# PiHAT_Sensor.net
KiCad netlist of a schematic drawn in Altium Designer
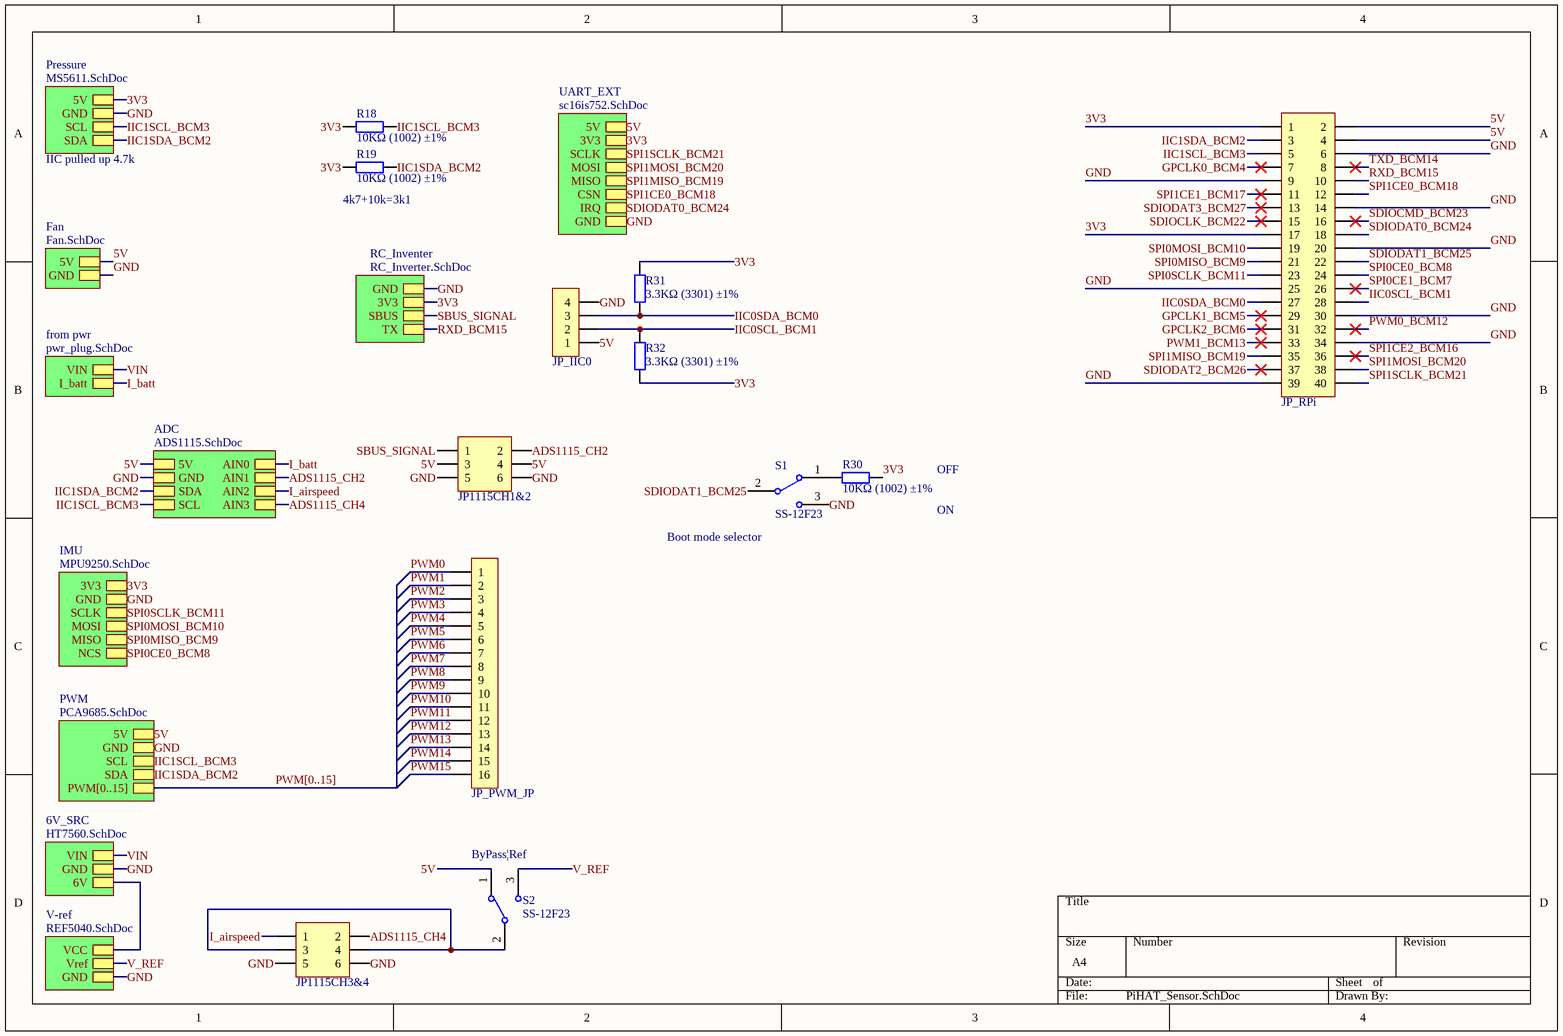
[diagram p0: PiHAT_Sensor.SchDoc]

(export (version "E")
  (design (tool "Eeschema 10.0.6"))
  (components
    (comp (ref "JP1115CH1&2")
      (value "Header3X2")
      (footprint "HDR2.54-WI-2x3P")
      (description "3*2P接插件")
      (fields (field (name "版权归属") "源创客"))
      (libsource (lib "4.5   - 接插件-脚距2.54") (part "Header 3X2"))
    )
    (comp (ref "JP1115CH3&4")
      (value "Header3X2")
      (footprint "HDR2.54-WI-2x3P")
      (description "3*2P接插件")
      (fields (field (name "版权归属") "源创客"))
      (libsource (lib "4.5   - 接插件-脚距2.54") (part "Header 3X2"))
    )
    (comp (ref "JP_IIC0")
      (value "HDR-1X4")
      (footprint "MX 1.25-WS-4P")
      (description "4P接插件")
      (fields (field (name "版权归属") "源创客"))
      (libsource (lib "4.2   - 接插件-脚距1.25") (part "Header 4"))
    )
    (comp (ref "JP_PWM_JP")
      (value "HDR-1X16")
      (footprint "HDR2.54-LI-16P")
      (description "16P接插件")
      (fields (field (name "版权归属") "源创客"))
      (libsource (lib "4.5   - 接插件-脚距2.54") (part "Header 16"))
    )
    (comp (ref "JP_RPi")
      (value "Header 2X11")
      (footprint "HDR2.54-LI-2x20P")
      (description "20*2P接插件")
      (fields (field (name "版权归属") "源创客"))
      (libsource (lib "4.5   - 接插件-脚距2.54") (part "Header 20X2"))
    )
    (comp (ref "R18")
      (value "10KΩ (1002) ±1%")
      (footprint "0402_R")
      (description "贴片电阻")
      (libsource (lib "Miscellaneous Devices LC") (part "0402 10KΩ (1002) 1%"))
    )
    (comp (ref "R19")
      (value "10KΩ (1002) ±1%")
      (footprint "0402_R")
      (description "贴片电阻")
      (libsource (lib "Miscellaneous Devices LC") (part "0402 10KΩ (1002) 1%"))
    )
    (comp (ref "R30")
      (value "10KΩ (1002) ±1%")
      (footprint "0402_R")
      (description "贴片电阻")
      (libsource (lib "Miscellaneous Devices LC") (part "0402 10KΩ (1002) 1%"))
    )
    (comp (ref "R31")
      (value "3.3KΩ (3301) ±1%")
      (footprint "0402_R")
      (description "贴片电阻")
      (libsource (lib "Miscellaneous Devices LC") (part "0402 3.3KΩ (3301) 1%"))
    )
    (comp (ref "R32")
      (value "3.3KΩ (3301) ±1%")
      (footprint "0402_R")
      (description "贴片电阻")
      (libsource (lib "Miscellaneous Devices LC") (part "0402 3.3KΩ (3301) 1%"))
    )
    (comp (ref "S1")
      (value "SS-12F23")
      (footprint "MSK-12C01-07")
      (description "1路波动开关")
      (fields (field (name "版权归属") "源创客"))
      (libsource (lib "5.1   - 按键-开关") (part "SSW-1P"))
    )
    (comp (ref "S2")
      (value "SS-12F23")
      (footprint "MSK-12C01-07")
      (description "1路波动开关")
      (fields (field (name "版权归属") "源创客"))
      (libsource (lib "5.1   - 按键-开关") (part "SSW-1P"))
    )
  )
  (nets
    (net (code "1") (name "/3V3") (class "Default")
      (node (ref "JP_RPi") (pin "1") (pinfunction "1_1") (pintype "passive"))
      (node (ref "JP_RPi") (pin "17") (pinfunction "17_17") (pintype "passive"))
      (node (ref "R18") (pin "1") (pinfunction "1_1") (pintype "passive"))
      (node (ref "R19") (pin "1") (pinfunction "1_1") (pintype "passive"))
      (node (ref "R30") (pin "2") (pinfunction "2_2") (pintype "passive"))
      (node (ref "R31") (pin "2") (pinfunction "2_2") (pintype "passive"))
      (node (ref "R32") (pin "1") (pinfunction "1_1") (pintype "passive"))
    )
    (net (code "2") (name "/5V") (class "Default")
      (node (ref "JP1115CH1&2") (pin "3") (pinfunction "3_3") (pintype "passive"))
      (node (ref "JP1115CH1&2") (pin "4") (pinfunction "4_4") (pintype "passive"))
      (node (ref "JP_IIC0") (pin "1") (pinfunction "1_1") (pintype "passive"))
      (node (ref "JP_RPi") (pin "2") (pinfunction "2_2") (pintype "passive"))
      (node (ref "JP_RPi") (pin "4") (pinfunction "4_4") (pintype "passive"))
      (node (ref "S2") (pin "1") (pinfunction "1_1") (pintype "passive"))
    )
    (net (code "4") (name "/ADS1115_CH2") (class "Default")
      (node (ref "JP1115CH1&2") (pin "2") (pinfunction "2_2") (pintype "passive"))
    )
    (net (code "5") (name "/ADS1115_CH4") (class "Default")
      (node (ref "JP1115CH3&4") (pin "2") (pinfunction "2_2") (pintype "passive"))
    )
    (net (code "6") (name "/GND") (class "Default")
      (node (ref "JP1115CH1&2") (pin "5") (pinfunction "5_5") (pintype "passive"))
      (node (ref "JP1115CH1&2") (pin "6") (pinfunction "6_6") (pintype "passive"))
      (node (ref "JP1115CH3&4") (pin "5") (pinfunction "5_5") (pintype "passive"))
      (node (ref "JP1115CH3&4") (pin "6") (pinfunction "6_6") (pintype "passive"))
      (node (ref "JP_IIC0") (pin "4") (pinfunction "4_4") (pintype "passive"))
      (node (ref "JP_RPi") (pin "14") (pinfunction "14_14") (pintype "passive"))
      (node (ref "JP_RPi") (pin "20") (pinfunction "20_20") (pintype "passive"))
      (node (ref "JP_RPi") (pin "25") (pinfunction "25_25") (pintype "passive"))
      (node (ref "JP_RPi") (pin "30") (pinfunction "30_30") (pintype "passive"))
      (node (ref "JP_RPi") (pin "34") (pinfunction "34_34") (pintype "passive"))
      (node (ref "JP_RPi") (pin "39") (pinfunction "39_39") (pintype "passive"))
      (node (ref "JP_RPi") (pin "6") (pinfunction "6_6") (pintype "passive"))
      (node (ref "JP_RPi") (pin "9") (pinfunction "9_9") (pintype "passive"))
      (node (ref "S1") (pin "3") (pinfunction "3_3") (pintype "passive"))
    )
    (net (code "7") (name "/GPCLK0_BCM4") (class "Default")
      (node (ref "JP_RPi") (pin "7") (pinfunction "7_7") (pintype "passive+no_connect"))
    )
    (net (code "8") (name "/GPCLK1_BCM5") (class "Default")
      (node (ref "JP_RPi") (pin "29") (pinfunction "29_29") (pintype "passive+no_connect"))
    )
    (net (code "9") (name "/GPCLK2_BCM6") (class "Default")
      (node (ref "JP_RPi") (pin "31") (pinfunction "31_31") (pintype "passive+no_connect"))
    )
    (net (code "10") (name "/IIC0SCL_BCM1") (class "Default")
      (node (ref "JP_IIC0") (pin "2") (pinfunction "2_2") (pintype "passive"))
      (node (ref "JP_RPi") (pin "28") (pinfunction "28_28") (pintype "passive"))
      (node (ref "R32") (pin "2") (pinfunction "2_2") (pintype "passive"))
    )
    (net (code "11") (name "/IIC0SDA_BCM0") (class "Default")
      (node (ref "JP_IIC0") (pin "3") (pinfunction "3_3") (pintype "passive"))
      (node (ref "JP_RPi") (pin "27") (pinfunction "27_27") (pintype "passive"))
      (node (ref "R31") (pin "1") (pinfunction "1_1") (pintype "passive"))
    )
    (net (code "12") (name "/IIC1SCL_BCM3") (class "Default")
      (node (ref "JP_RPi") (pin "5") (pinfunction "5_5") (pintype "passive"))
      (node (ref "R18") (pin "2") (pinfunction "2_2") (pintype "passive"))
    )
    (net (code "13") (name "/IIC1SDA_BCM2") (class "Default")
      (node (ref "JP_RPi") (pin "3") (pinfunction "3_3") (pintype "passive"))
      (node (ref "R19") (pin "2") (pinfunction "2_2") (pintype "passive"))
    )
    (net (code "14") (name "/I_airspeed") (class "Default")
      (node (ref "JP1115CH3&4") (pin "1") (pinfunction "1_1") (pintype "passive"))
    )
    (net (code "16") (name "/PWM0") (class "Default")
      (node (ref "JP_PWM_JP") (pin "1") (pinfunction "1_1") (pintype "passive"))
    )
    (net (code "17") (name "/PWM0_BCM12") (class "Default")
      (node (ref "JP_RPi") (pin "32") (pinfunction "32_32") (pintype "passive+no_connect"))
    )
    (net (code "18") (name "/PWM1") (class "Default")
      (node (ref "JP_PWM_JP") (pin "2") (pinfunction "2_2") (pintype "passive"))
    )
    (net (code "19") (name "/PWM1_BCM13") (class "Default")
      (node (ref "JP_RPi") (pin "33") (pinfunction "33_33") (pintype "passive+no_connect"))
    )
    (net (code "20") (name "/PWM2") (class "Default")
      (node (ref "JP_PWM_JP") (pin "3") (pinfunction "3_3") (pintype "passive"))
    )
    (net (code "21") (name "/PWM3") (class "Default")
      (node (ref "JP_PWM_JP") (pin "4") (pinfunction "4_4") (pintype "passive"))
    )
    (net (code "22") (name "/PWM4") (class "Default")
      (node (ref "JP_PWM_JP") (pin "5") (pinfunction "5_5") (pintype "passive"))
    )
    (net (code "23") (name "/PWM5") (class "Default")
      (node (ref "JP_PWM_JP") (pin "6") (pinfunction "6_6") (pintype "passive"))
    )
    (net (code "24") (name "/PWM6") (class "Default")
      (node (ref "JP_PWM_JP") (pin "7") (pinfunction "7_7") (pintype "passive"))
    )
    (net (code "25") (name "/PWM7") (class "Default")
      (node (ref "JP_PWM_JP") (pin "8") (pinfunction "8_8") (pintype "passive"))
    )
    (net (code "26") (name "/PWM8") (class "Default")
      (node (ref "JP_PWM_JP") (pin "9") (pinfunction "9_9") (pintype "passive"))
    )
    (net (code "27") (name "/PWM9") (class "Default")
      (node (ref "JP_PWM_JP") (pin "10") (pinfunction "10_10") (pintype "passive"))
    )
    (net (code "28") (name "/PWM10") (class "Default")
      (node (ref "JP_PWM_JP") (pin "11") (pinfunction "11_11") (pintype "passive"))
    )
    (net (code "29") (name "/PWM11") (class "Default")
      (node (ref "JP_PWM_JP") (pin "12") (pinfunction "12_12") (pintype "passive"))
    )
    (net (code "30") (name "/PWM12") (class "Default")
      (node (ref "JP_PWM_JP") (pin "13") (pinfunction "13_13") (pintype "passive"))
    )
    (net (code "31") (name "/PWM13") (class "Default")
      (node (ref "JP_PWM_JP") (pin "14") (pinfunction "14_14") (pintype "passive"))
    )
    (net (code "32") (name "/PWM14") (class "Default")
      (node (ref "JP_PWM_JP") (pin "15") (pinfunction "15_15") (pintype "passive"))
    )
    (net (code "33") (name "/PWM15") (class "Default")
      (node (ref "JP_PWM_JP") (pin "16") (pinfunction "16_16") (pintype "passive"))
    )
    (net (code "35") (name "/RXD_BCM15") (class "Default")
      (node (ref "JP_RPi") (pin "10") (pinfunction "10_10") (pintype "passive"))
    )
    (net (code "36") (name "/SBUS_SIGNAL") (class "Default")
      (node (ref "JP1115CH1&2") (pin "1") (pinfunction "1_1") (pintype "passive"))
    )
    (net (code "37") (name "/SDIOCLK_BCM22") (class "Default")
      (node (ref "JP_RPi") (pin "15") (pinfunction "15_15") (pintype "passive+no_connect"))
    )
    (net (code "38") (name "/SDIOCMD_BCM23") (class "Default")
      (node (ref "JP_RPi") (pin "16") (pinfunction "16_16") (pintype "passive+no_connect"))
    )
    (net (code "39") (name "/SDIODAT0_BCM24") (class "Default")
      (node (ref "JP_RPi") (pin "18") (pinfunction "18_18") (pintype "passive"))
    )
    (net (code "40") (name "/SDIODAT1_BCM25") (class "Default")
      (node (ref "JP_RPi") (pin "22") (pinfunction "22_22") (pintype "passive"))
      (node (ref "S1") (pin "2") (pinfunction "2_2") (pintype "passive"))
    )
    (net (code "41") (name "/SDIODAT2_BCM26") (class "Default")
      (node (ref "JP_RPi") (pin "37") (pinfunction "37_37") (pintype "passive+no_connect"))
    )
    (net (code "42") (name "/SDIODAT3_BCM27") (class "Default")
      (node (ref "JP_RPi") (pin "13") (pinfunction "13_13") (pintype "passive+no_connect"))
    )
    (net (code "43") (name "/SPI0CE0_BCM8") (class "Default")
      (node (ref "JP_RPi") (pin "24") (pinfunction "24_24") (pintype "passive"))
    )
    (net (code "44") (name "/SPI0CE1_BCM7") (class "Default")
      (node (ref "JP_RPi") (pin "26") (pinfunction "26_26") (pintype "passive+no_connect"))
    )
    (net (code "45") (name "/SPI0MISO_BCM9") (class "Default")
      (node (ref "JP_RPi") (pin "21") (pinfunction "21_21") (pintype "passive"))
    )
    (net (code "46") (name "/SPI0MOSI_BCM10") (class "Default")
      (node (ref "JP_RPi") (pin "19") (pinfunction "19_19") (pintype "passive"))
    )
    (net (code "47") (name "/SPI0SCLK_BCM11") (class "Default")
      (node (ref "JP_RPi") (pin "23") (pinfunction "23_23") (pintype "passive"))
    )
    (net (code "48") (name "/SPI1CE0_BCM18") (class "Default")
      (node (ref "JP_RPi") (pin "12") (pinfunction "12_12") (pintype "passive"))
    )
    (net (code "49") (name "/SPI1CE1_BCM17") (class "Default")
      (node (ref "JP_RPi") (pin "11") (pinfunction "11_11") (pintype "passive+no_connect"))
    )
    (net (code "50") (name "/SPI1CE2_BCM16") (class "Default")
      (node (ref "JP_RPi") (pin "36") (pinfunction "36_36") (pintype "passive+no_connect"))
    )
    (net (code "51") (name "/SPI1MISO_BCM19") (class "Default")
      (node (ref "JP_RPi") (pin "35") (pinfunction "35_35") (pintype "passive"))
    )
    (net (code "52") (name "/SPI1MOSI_BCM20") (class "Default")
      (node (ref "JP_RPi") (pin "38") (pinfunction "38_38") (pintype "passive"))
    )
    (net (code "53") (name "/SPI1SCLK_BCM21") (class "Default")
      (node (ref "JP_RPi") (pin "40") (pinfunction "40_40") (pintype "passive"))
    )
    (net (code "54") (name "/TXD_BCM14") (class "Default")
      (node (ref "JP_RPi") (pin "8") (pinfunction "8_8") (pintype "passive+no_connect"))
    )
    (net (code "56") (name "/V_REF") (class "Default")
      (node (ref "S2") (pin "3") (pinfunction "3_3") (pintype "passive"))
    )
    (net (code "57") (name "Net-(JP1115CH3&4-Pad3)") (class "Default")
      (node (ref "JP1115CH3&4") (pin "3") (pinfunction "3_3") (pintype "passive"))
      (node (ref "JP1115CH3&4") (pin "4") (pinfunction "4_4") (pintype "passive"))
      (node (ref "S2") (pin "2") (pinfunction "2_2") (pintype "passive"))
    )
    (net (code "58") (name "Net-(R30-Pad1)") (class "Default")
      (node (ref "R30") (pin "1") (pinfunction "1_1") (pintype "passive"))
      (node (ref "S1") (pin "1") (pinfunction "1_1") (pintype "passive"))
    )
  )
)
